# atxmega128d3_breakout.net
KiCad netlist of a schematic drawn in EAGLE
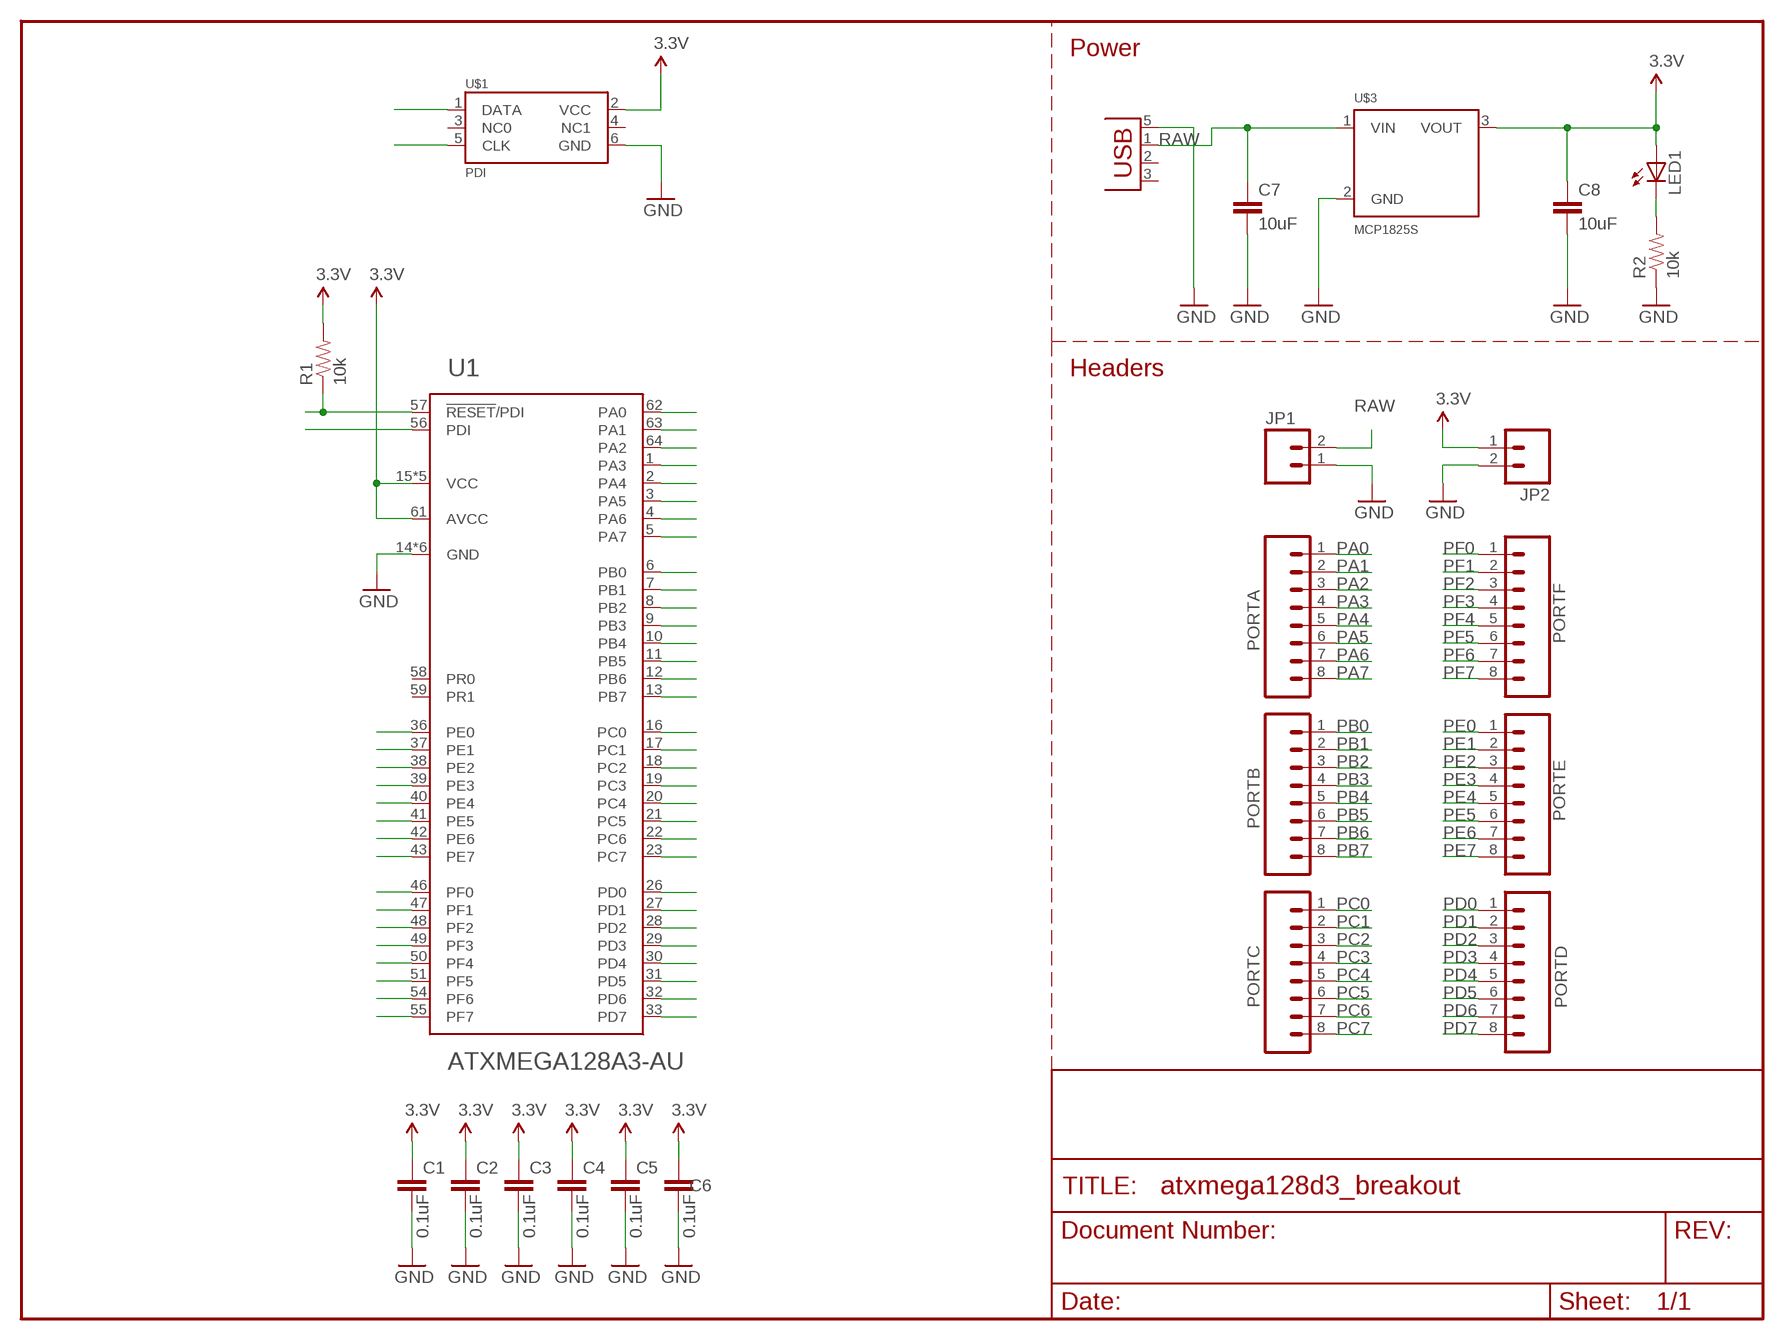
[diagram p0: schematic, sheet 1]

(export (version "E")
  (design (tool "Eeschema 10.0.6"))
  (components
    (comp (ref "C1")
      (value "0.1uF")
      (footprint "eagle-import:0805")
      (libsource (lib "eagle-import") (part "CAP0805"))
    )
    (comp (ref "C2")
      (value "0.1uF")
      (footprint "eagle-import:0805")
      (libsource (lib "eagle-import") (part "CAP0805"))
    )
    (comp (ref "C3")
      (value "0.1uF")
      (footprint "eagle-import:0805")
      (libsource (lib "eagle-import") (part "CAP0805"))
    )
    (comp (ref "C4")
      (value "0.1uF")
      (footprint "eagle-import:0805")
      (libsource (lib "eagle-import") (part "CAP0805"))
    )
    (comp (ref "C5")
      (value "0.1uF")
      (footprint "eagle-import:0805")
      (libsource (lib "eagle-import") (part "CAP0805"))
    )
    (comp (ref "C6")
      (value "0.1uF")
      (footprint "eagle-import:0805")
      (libsource (lib "eagle-import") (part "CAP0805"))
    )
    (comp (ref "C7")
      (value "10uF")
      (footprint "eagle-import:0805")
      (libsource (lib "eagle-import") (part "CAP0805"))
    )
    (comp (ref "C8")
      (value "10uF")
      (footprint "eagle-import:0805")
      (libsource (lib "eagle-import") (part "CAP0805"))
    )
    (comp (ref "JP1")
      (value "M02PTH")
      (footprint "eagle-import:1X02")
      (libsource (lib "eagle-import") (part "M02PTH"))
    )
    (comp (ref "JP2")
      (value "M02PTH")
      (footprint "eagle-import:1X02")
      (libsource (lib "eagle-import") (part "M02PTH"))
    )
    (comp (ref "LED1")
      (value "LEDCHIP-LED0805")
      (footprint "eagle-import:CHIP-LED0805")
      (libsource (lib "eagle-import") (part "LEDCHIP-LED0805"))
    )
    (comp (ref "PORTA")
      (value "M081X08")
      (footprint "eagle-import:1X08")
      (libsource (lib "eagle-import") (part "M081X08"))
    )
    (comp (ref "PORTB")
      (value "M081X08")
      (footprint "eagle-import:1X08")
      (libsource (lib "eagle-import") (part "M081X08"))
    )
    (comp (ref "PORTC")
      (value "M081X08")
      (footprint "eagle-import:1X08")
      (libsource (lib "eagle-import") (part "M081X08"))
    )
    (comp (ref "PORTD")
      (value "M081X08")
      (footprint "eagle-import:1X08")
      (libsource (lib "eagle-import") (part "M081X08"))
    )
    (comp (ref "PORTE")
      (value "M081X08")
      (footprint "eagle-import:1X08")
      (libsource (lib "eagle-import") (part "M081X08"))
    )
    (comp (ref "PORTF")
      (value "M081X08")
      (footprint "eagle-import:1X08")
      (libsource (lib "eagle-import") (part "M081X08"))
    )
    (comp (ref "R1")
      (value "10k")
      (footprint "eagle-import:0805")
      (libsource (lib "eagle-import") (part "RESISTOR0805-RES"))
    )
    (comp (ref "R2")
      (value "10k")
      (footprint "eagle-import:0805")
      (libsource (lib "eagle-import") (part "RESISTOR0805-RES"))
    )
    (comp (ref "U$1")
      (value "PDI")
      (footprint "eagle-import:2X3")
      (libsource (lib "eagle-import") (part "PDI"))
    )
    (comp (ref "U$2")
      (value "USB")
      (footprint "eagle-import:USB_MICRO_B")
      (libsource (lib "eagle-import") (part "USB"))
    )
    (comp (ref "U$3")
      (value "MCP1825S")
      (footprint "eagle-import:SOT233")
      (libsource (lib "eagle-import") (part "MCP1825S"))
    )
    (comp (ref "U1")
      (value "ATXMEGA128A3-AU")
      (footprint "eagle-import:TQFP-64A-64")
      (libsource (lib "eagle-import") (part "ATXMEGA128A3-AU"))
    )
  )
  (nets
    (net (code "1") (name "/CLK") (class "Default")
      (node (ref "R1") (pin "1") (pinfunction "1_1") (pintype "passive"))
      (node (ref "U$1") (pin "5") (pinfunction "CLK_5") (pintype "bidirectional"))
      (node (ref "U1") (pin "57") (pinfunction "~{RESET}/PDI_57") (pintype "bidirectional"))
    )
    (net (code "2") (name "/DATA") (class "Default")
      (node (ref "U$1") (pin "1") (pinfunction "DATA_1") (pintype "bidirectional"))
      (node (ref "U1") (pin "56") (pinfunction "PDI_56") (pintype "bidirectional"))
    )
    (net (code "3") (name "/PA0") (class "Default")
      (node (ref "PORTA") (pin "1") (pinfunction "1_1") (pintype "passive"))
      (node (ref "U1") (pin "62") (pinfunction "PA0_62") (pintype "bidirectional"))
    )
    (net (code "4") (name "/PA1") (class "Default")
      (node (ref "PORTA") (pin "2") (pinfunction "2_2") (pintype "passive"))
      (node (ref "U1") (pin "63") (pinfunction "PA1_63") (pintype "bidirectional"))
    )
    (net (code "5") (name "/PA2") (class "Default")
      (node (ref "PORTA") (pin "3") (pinfunction "3_3") (pintype "passive"))
      (node (ref "U1") (pin "64") (pinfunction "PA2_64") (pintype "bidirectional"))
    )
    (net (code "6") (name "/PA3") (class "Default")
      (node (ref "PORTA") (pin "4") (pinfunction "4_4") (pintype "passive"))
      (node (ref "U1") (pin "1") (pinfunction "PA3_1") (pintype "bidirectional"))
    )
    (net (code "7") (name "/PA4") (class "Default")
      (node (ref "PORTA") (pin "5") (pinfunction "5_5") (pintype "passive"))
      (node (ref "U1") (pin "2") (pinfunction "PA4_2") (pintype "bidirectional"))
    )
    (net (code "8") (name "/PA5") (class "Default")
      (node (ref "PORTA") (pin "6") (pinfunction "6_6") (pintype "passive"))
      (node (ref "U1") (pin "3") (pinfunction "PA5_3") (pintype "bidirectional"))
    )
    (net (code "9") (name "/PA6") (class "Default")
      (node (ref "PORTA") (pin "7") (pinfunction "7_7") (pintype "passive"))
      (node (ref "U1") (pin "4") (pinfunction "PA6_4") (pintype "bidirectional"))
    )
    (net (code "10") (name "/PA7") (class "Default")
      (node (ref "PORTA") (pin "8") (pinfunction "8_8") (pintype "passive"))
      (node (ref "U1") (pin "5") (pinfunction "PA7_5") (pintype "bidirectional"))
    )
    (net (code "11") (name "/PB0") (class "Default")
      (node (ref "PORTB") (pin "1") (pinfunction "1_1") (pintype "passive"))
      (node (ref "U1") (pin "6") (pinfunction "PB0_6") (pintype "bidirectional"))
    )
    (net (code "12") (name "/PB1") (class "Default")
      (node (ref "PORTB") (pin "2") (pinfunction "2_2") (pintype "passive"))
      (node (ref "U1") (pin "7") (pinfunction "PB1_7") (pintype "bidirectional"))
    )
    (net (code "13") (name "/PB2") (class "Default")
      (node (ref "PORTB") (pin "3") (pinfunction "3_3") (pintype "passive"))
      (node (ref "U1") (pin "8") (pinfunction "PB2_8") (pintype "bidirectional"))
    )
    (net (code "14") (name "/PB3") (class "Default")
      (node (ref "PORTB") (pin "4") (pinfunction "4_4") (pintype "passive"))
      (node (ref "U1") (pin "9") (pinfunction "PB3_9") (pintype "bidirectional"))
    )
    (net (code "15") (name "/PB4") (class "Default")
      (node (ref "PORTB") (pin "5") (pinfunction "5_5") (pintype "passive"))
      (node (ref "U1") (pin "10") (pinfunction "PB4_10") (pintype "bidirectional"))
    )
    (net (code "16") (name "/PB5") (class "Default")
      (node (ref "PORTB") (pin "6") (pinfunction "6_6") (pintype "passive"))
      (node (ref "U1") (pin "11") (pinfunction "PB5_11") (pintype "bidirectional"))
    )
    (net (code "17") (name "/PB6") (class "Default")
      (node (ref "PORTB") (pin "7") (pinfunction "7_7") (pintype "passive"))
      (node (ref "U1") (pin "12") (pinfunction "PB6_12") (pintype "bidirectional"))
    )
    (net (code "18") (name "/PB7") (class "Default")
      (node (ref "PORTB") (pin "8") (pinfunction "8_8") (pintype "passive"))
      (node (ref "U1") (pin "13") (pinfunction "PB7_13") (pintype "bidirectional"))
    )
    (net (code "19") (name "/PC0") (class "Default")
      (node (ref "PORTC") (pin "1") (pinfunction "1_1") (pintype "passive"))
      (node (ref "U1") (pin "16") (pinfunction "PC0_16") (pintype "bidirectional"))
    )
    (net (code "20") (name "/PC1") (class "Default")
      (node (ref "PORTC") (pin "2") (pinfunction "2_2") (pintype "passive"))
      (node (ref "U1") (pin "17") (pinfunction "PC1_17") (pintype "bidirectional"))
    )
    (net (code "21") (name "/PC2") (class "Default")
      (node (ref "PORTC") (pin "3") (pinfunction "3_3") (pintype "passive"))
      (node (ref "U1") (pin "18") (pinfunction "PC2_18") (pintype "bidirectional"))
    )
    (net (code "22") (name "/PC3") (class "Default")
      (node (ref "PORTC") (pin "4") (pinfunction "4_4") (pintype "passive"))
      (node (ref "U1") (pin "19") (pinfunction "PC3_19") (pintype "bidirectional"))
    )
    (net (code "23") (name "/PC4") (class "Default")
      (node (ref "PORTC") (pin "5") (pinfunction "5_5") (pintype "passive"))
      (node (ref "U1") (pin "20") (pinfunction "PC4_20") (pintype "bidirectional"))
    )
    (net (code "24") (name "/PC5") (class "Default")
      (node (ref "PORTC") (pin "6") (pinfunction "6_6") (pintype "passive"))
      (node (ref "U1") (pin "21") (pinfunction "PC5_21") (pintype "bidirectional"))
    )
    (net (code "25") (name "/PC6") (class "Default")
      (node (ref "PORTC") (pin "7") (pinfunction "7_7") (pintype "passive"))
      (node (ref "U1") (pin "22") (pinfunction "PC6_22") (pintype "bidirectional"))
    )
    (net (code "26") (name "/PC7") (class "Default")
      (node (ref "PORTC") (pin "8") (pinfunction "8_8") (pintype "passive"))
      (node (ref "U1") (pin "23") (pinfunction "PC7_23") (pintype "bidirectional"))
    )
    (net (code "27") (name "/PD0") (class "Default")
      (node (ref "PORTD") (pin "1") (pinfunction "1_1") (pintype "passive"))
      (node (ref "U1") (pin "26") (pinfunction "PD0_26") (pintype "bidirectional"))
    )
    (net (code "28") (name "/PD1") (class "Default")
      (node (ref "PORTD") (pin "2") (pinfunction "2_2") (pintype "passive"))
      (node (ref "U1") (pin "27") (pinfunction "PD1_27") (pintype "bidirectional"))
    )
    (net (code "29") (name "/PD2") (class "Default")
      (node (ref "PORTD") (pin "3") (pinfunction "3_3") (pintype "passive"))
      (node (ref "U1") (pin "28") (pinfunction "PD2_28") (pintype "bidirectional"))
    )
    (net (code "30") (name "/PD3") (class "Default")
      (node (ref "PORTD") (pin "4") (pinfunction "4_4") (pintype "passive"))
      (node (ref "U1") (pin "29") (pinfunction "PD3_29") (pintype "bidirectional"))
    )
    (net (code "31") (name "/PD4") (class "Default")
      (node (ref "PORTD") (pin "5") (pinfunction "5_5") (pintype "passive"))
      (node (ref "U1") (pin "30") (pinfunction "PD4_30") (pintype "bidirectional"))
    )
    (net (code "32") (name "/PD5") (class "Default")
      (node (ref "PORTD") (pin "6") (pinfunction "6_6") (pintype "passive"))
      (node (ref "U1") (pin "31") (pinfunction "PD5_31") (pintype "bidirectional"))
    )
    (net (code "33") (name "/PD6") (class "Default")
      (node (ref "PORTD") (pin "7") (pinfunction "7_7") (pintype "passive"))
      (node (ref "U1") (pin "32") (pinfunction "PD6_32") (pintype "bidirectional"))
    )
    (net (code "34") (name "/PD7") (class "Default")
      (node (ref "PORTD") (pin "8") (pinfunction "8_8") (pintype "passive"))
      (node (ref "U1") (pin "33") (pinfunction "PD7_33") (pintype "bidirectional"))
    )
    (net (code "35") (name "/PE0") (class "Default")
      (node (ref "PORTE") (pin "1") (pinfunction "1_1") (pintype "passive"))
      (node (ref "U1") (pin "36") (pinfunction "PE0_36") (pintype "bidirectional"))
    )
    (net (code "36") (name "/PE1") (class "Default")
      (node (ref "PORTE") (pin "2") (pinfunction "2_2") (pintype "passive"))
      (node (ref "U1") (pin "37") (pinfunction "PE1_37") (pintype "bidirectional"))
    )
    (net (code "37") (name "/PE2") (class "Default")
      (node (ref "PORTE") (pin "3") (pinfunction "3_3") (pintype "passive"))
      (node (ref "U1") (pin "38") (pinfunction "PE2_38") (pintype "bidirectional"))
    )
    (net (code "38") (name "/PE3") (class "Default")
      (node (ref "PORTE") (pin "4") (pinfunction "4_4") (pintype "passive"))
      (node (ref "U1") (pin "39") (pinfunction "PE3_39") (pintype "bidirectional"))
    )
    (net (code "39") (name "/PE4") (class "Default")
      (node (ref "PORTE") (pin "5") (pinfunction "5_5") (pintype "passive"))
      (node (ref "U1") (pin "40") (pinfunction "PE4_40") (pintype "bidirectional"))
    )
    (net (code "40") (name "/PE5") (class "Default")
      (node (ref "PORTE") (pin "6") (pinfunction "6_6") (pintype "passive"))
      (node (ref "U1") (pin "41") (pinfunction "PE5_41") (pintype "bidirectional"))
    )
    (net (code "41") (name "/PE6") (class "Default")
      (node (ref "PORTE") (pin "7") (pinfunction "7_7") (pintype "passive"))
      (node (ref "U1") (pin "42") (pinfunction "PE6_42") (pintype "bidirectional"))
    )
    (net (code "42") (name "/PE7") (class "Default")
      (node (ref "PORTE") (pin "8") (pinfunction "8_8") (pintype "passive"))
      (node (ref "U1") (pin "43") (pinfunction "PE7_43") (pintype "bidirectional"))
    )
    (net (code "43") (name "/PF0") (class "Default")
      (node (ref "PORTF") (pin "1") (pinfunction "1_1") (pintype "passive"))
      (node (ref "U1") (pin "46") (pinfunction "PF0_46") (pintype "bidirectional"))
    )
    (net (code "44") (name "/PF1") (class "Default")
      (node (ref "PORTF") (pin "2") (pinfunction "2_2") (pintype "passive"))
      (node (ref "U1") (pin "47") (pinfunction "PF1_47") (pintype "bidirectional"))
    )
    (net (code "45") (name "/PF2") (class "Default")
      (node (ref "PORTF") (pin "3") (pinfunction "3_3") (pintype "passive"))
      (node (ref "U1") (pin "48") (pinfunction "PF2_48") (pintype "bidirectional"))
    )
    (net (code "46") (name "/PF3") (class "Default")
      (node (ref "PORTF") (pin "4") (pinfunction "4_4") (pintype "passive"))
      (node (ref "U1") (pin "49") (pinfunction "PF3_49") (pintype "bidirectional"))
    )
    (net (code "47") (name "/PF4") (class "Default")
      (node (ref "PORTF") (pin "5") (pinfunction "5_5") (pintype "passive"))
      (node (ref "U1") (pin "50") (pinfunction "PF4_50") (pintype "bidirectional"))
    )
    (net (code "48") (name "/PF5") (class "Default")
      (node (ref "PORTF") (pin "6") (pinfunction "6_6") (pintype "passive"))
      (node (ref "U1") (pin "51") (pinfunction "PF5_51") (pintype "bidirectional"))
    )
    (net (code "49") (name "/PF6") (class "Default")
      (node (ref "PORTF") (pin "7") (pinfunction "7_7") (pintype "passive"))
      (node (ref "U1") (pin "54") (pinfunction "PF6_54") (pintype "bidirectional"))
    )
    (net (code "50") (name "/PF7") (class "Default")
      (node (ref "PORTF") (pin "8") (pinfunction "8_8") (pintype "passive"))
      (node (ref "U1") (pin "55") (pinfunction "PF7_55") (pintype "bidirectional"))
    )
    (net (code "51") (name "/RAW") (class "Default")
      (node (ref "C7") (pin "1") (pinfunction "1_1") (pintype "passive"))
      (node (ref "JP1") (pin "2") (pinfunction "2_2") (pintype "passive"))
      (node (ref "U$2") (pin "1") (pinfunction "VBUS_1") (pintype "bidirectional"))
      (node (ref "U$3") (pin "1") (pinfunction "VIN_1") (pintype "bidirectional"))
    )
    (net (code "52") (name "3.3V") (class "Default")
      (node (ref "C1") (pin "1") (pinfunction "1_1") (pintype "passive"))
      (node (ref "C2") (pin "1") (pinfunction "1_1") (pintype "passive"))
      (node (ref "C3") (pin "1") (pinfunction "1_1") (pintype "passive"))
      (node (ref "C4") (pin "1") (pinfunction "1_1") (pintype "passive"))
      (node (ref "C5") (pin "1") (pinfunction "1_1") (pintype "passive"))
      (node (ref "C6") (pin "1") (pinfunction "1_1") (pintype "passive"))
      (node (ref "C8") (pin "1") (pinfunction "1_1") (pintype "passive"))
      (node (ref "JP2") (pin "1") (pinfunction "1_1") (pintype "passive"))
      (node (ref "LED1") (pin "A") (pinfunction "A_A") (pintype "passive"))
      (node (ref "R1") (pin "2") (pinfunction "2_2") (pintype "passive"))
      (node (ref "U$1") (pin "2") (pinfunction "VCC_2") (pintype "bidirectional"))
      (node (ref "U$3") (pin "3") (pinfunction "VOUT_3") (pintype "bidirectional"))
      (node (ref "U1") (pin "15") (pinfunction "VCC_15") (pintype "power_in"))
      (node (ref "U1") (pin "25") (pinfunction "VCC_25") (pintype "power_in"))
      (node (ref "U1") (pin "35") (pinfunction "VCC_35") (pintype "power_in"))
      (node (ref "U1") (pin "45") (pinfunction "VCC_45") (pintype "power_in"))
      (node (ref "U1") (pin "53") (pinfunction "VCC_53") (pintype "power_in"))
      (node (ref "U1") (pin "61") (pinfunction "AVCC_61") (pintype "power_in"))
    )
    (net (code "53") (name "GND") (class "Default")
      (node (ref "C1") (pin "2") (pinfunction "2_2") (pintype "passive"))
      (node (ref "C2") (pin "2") (pinfunction "2_2") (pintype "passive"))
      (node (ref "C3") (pin "2") (pinfunction "2_2") (pintype "passive"))
      (node (ref "C4") (pin "2") (pinfunction "2_2") (pintype "passive"))
      (node (ref "C5") (pin "2") (pinfunction "2_2") (pintype "passive"))
      (node (ref "C6") (pin "2") (pinfunction "2_2") (pintype "passive"))
      (node (ref "C7") (pin "2") (pinfunction "2_2") (pintype "passive"))
      (node (ref "C8") (pin "2") (pinfunction "2_2") (pintype "passive"))
      (node (ref "JP1") (pin "1") (pinfunction "1_1") (pintype "passive"))
      (node (ref "JP2") (pin "2") (pinfunction "2_2") (pintype "passive"))
      (node (ref "R2") (pin "1") (pinfunction "1_1") (pintype "passive"))
      (node (ref "U$1") (pin "6") (pinfunction "GND_6") (pintype "bidirectional"))
      (node (ref "U$2") (pin "5") (pinfunction "GND_5") (pintype "bidirectional"))
      (node (ref "U$3") (pin "2") (pinfunction "GND_2") (pintype "bidirectional"))
      (node (ref "U1") (pin "14") (pinfunction "GND_14") (pintype "power_in"))
      (node (ref "U1") (pin "24") (pinfunction "GND_24") (pintype "power_in"))
      (node (ref "U1") (pin "34") (pinfunction "GND_34") (pintype "power_in"))
      (node (ref "U1") (pin "44") (pinfunction "GND_44") (pintype "power_in"))
      (node (ref "U1") (pin "52") (pinfunction "GND_52") (pintype "power_in"))
      (node (ref "U1") (pin "60") (pinfunction "GND_60") (pintype "power_in"))
    )
    (net (code "54") (name "Net-(LED1-PadC)") (class "Default")
      (node (ref "LED1") (pin "C") (pinfunction "C_C") (pintype "passive"))
      (node (ref "R2") (pin "2") (pinfunction "2_2") (pintype "passive"))
    )
    (net (code "55") (name "unconnected-(U$1-NC0-Pad3)") (class "Default")
      (node (ref "U$1") (pin "3") (pinfunction "NC0_3") (pintype "bidirectional"))
    )
    (net (code "56") (name "unconnected-(U$1-NC1-Pad4)") (class "Default")
      (node (ref "U$1") (pin "4") (pinfunction "NC1_4") (pintype "bidirectional"))
    )
    (net (code "57") (name "unconnected-(U$2-D+-Pad3)") (class "Default")
      (node (ref "U$2") (pin "3") (pinfunction "D+_3") (pintype "bidirectional"))
    )
    (net (code "58") (name "unconnected-(U$2-D--Pad2)") (class "Default")
      (node (ref "U$2") (pin "2") (pinfunction "D-_2") (pintype "bidirectional"))
    )
    (net (code "59") (name "unconnected-(U1-PR0-Pad58)") (class "Default")
      (node (ref "U1") (pin "58") (pinfunction "PR0_58") (pintype "bidirectional"))
    )
    (net (code "60") (name "unconnected-(U1-PR1-Pad59)") (class "Default")
      (node (ref "U1") (pin "59") (pinfunction "PR1_59") (pintype "bidirectional"))
    )
  )
)
